# flowerfriend_rev4.net
KiCad netlist of a schematic drawn in EAGLE
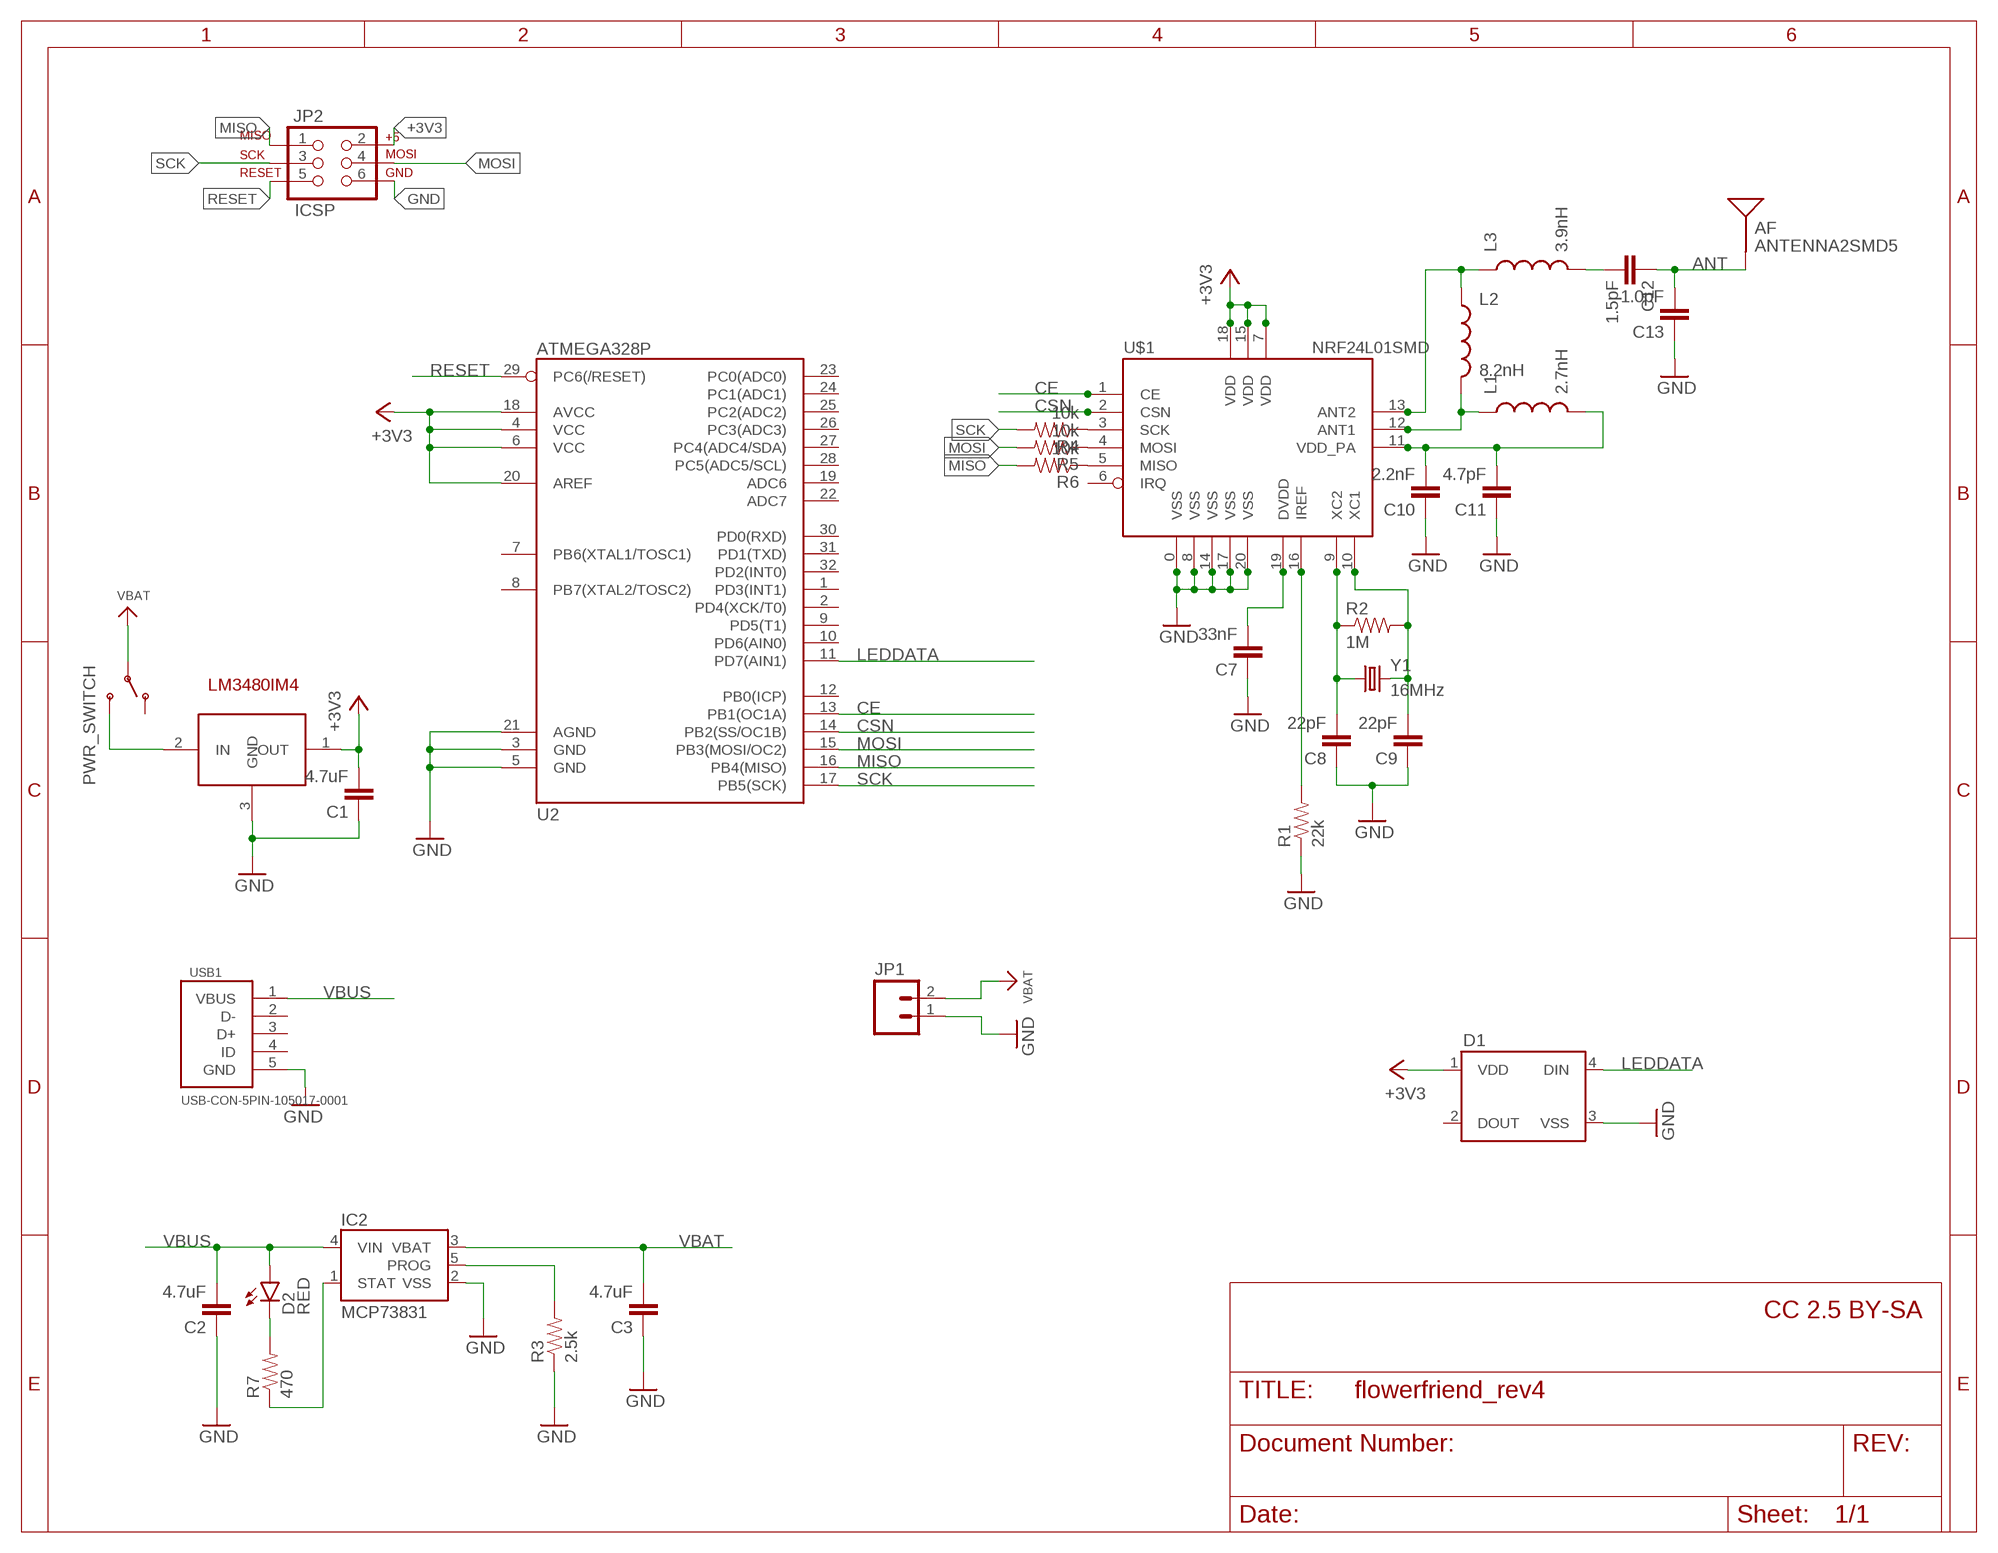
[diagram p0: schematic, sheet 1]

(export (version "E")
  (design (tool "Eeschema 10.0.6"))
  (components
    (comp (ref "AF")
      (value "ANTENNA2SMD5")
      (footprint "eagle-import:ANTENNA-CHIP5")
      (libsource (lib "eagle-import") (part "ANTENNA2SMD5"))
    )
    (comp (ref "C1")
      (value "4.7uF")
      (footprint "eagle-import:0805")
      (libsource (lib "eagle-import") (part "CAP0805"))
    )
    (comp (ref "C2")
      (value "4.7uF")
      (footprint "eagle-import:0805")
      (libsource (lib "eagle-import") (part "CAP0805"))
    )
    (comp (ref "C3")
      (value "4.7uF")
      (footprint "eagle-import:0805")
      (libsource (lib "eagle-import") (part "CAP0805"))
    )
    (comp (ref "C7")
      (value "33nF")
      (footprint "eagle-import:0805")
      (libsource (lib "eagle-import") (part "CAP0805"))
    )
    (comp (ref "C8")
      (value "22pF")
      (footprint "eagle-import:0805")
      (libsource (lib "eagle-import") (part "CAP0805"))
    )
    (comp (ref "C9")
      (value "22pF")
      (footprint "eagle-import:0805")
      (libsource (lib "eagle-import") (part "CAP0805"))
    )
    (comp (ref "C10")
      (value "2.2nF")
      (footprint "eagle-import:0805")
      (libsource (lib "eagle-import") (part "CAP0805"))
    )
    (comp (ref "C11")
      (value "4.7pF")
      (footprint "eagle-import:0805")
      (libsource (lib "eagle-import") (part "CAP0805"))
    )
    (comp (ref "C12")
      (value "1.5pF")
      (footprint "eagle-import:0805")
      (libsource (lib "eagle-import") (part "CAP0805"))
    )
    (comp (ref "C13")
      (value "1.0pF")
      (footprint "eagle-import:0805")
      (libsource (lib "eagle-import") (part "CAP0805"))
    )
    (comp (ref "D1")
      (value "WS2812B")
      (footprint "eagle-import:WS2812B")
      (libsource (lib "eagle-import") (part "WS2812B"))
    )
    (comp (ref "D2")
      (value "RED")
      (footprint "eagle-import:LED-0603")
      (libsource (lib "eagle-import") (part "LED-RED0603"))
    )
    (comp (ref "IC1")
      (value "LM3480IM4")
      (footprint "eagle-import:SOT23-3")
      (libsource (lib "eagle-import") (part "LM3480IM4"))
    )
    (comp (ref "IC2")
      (value "MCP73831")
      (footprint "eagle-import:SOT23-5")
      (libsource (lib "eagle-import") (part "MCP73831"))
    )
    (comp (ref "JP1")
      (value "M02PTH")
      (footprint "eagle-import:1X02")
      (libsource (lib "eagle-import") (part "M02PTH"))
    )
    (comp (ref "JP2")
      (value "ICSP")
      (footprint "eagle-import:2X3")
      (libsource (lib "eagle-import") (part "AVR_SPI_PRG_6PTH"))
    )
    (comp (ref "L1")
      (value "2.7nH")
      (footprint "eagle-import:0805")
      (libsource (lib "eagle-import") (part "INDUCTOR0805"))
    )
    (comp (ref "L2")
      (value "8.2nH")
      (footprint "eagle-import:0805")
      (libsource (lib "eagle-import") (part "INDUCTOR0805"))
    )
    (comp (ref "L3")
      (value "3.9nH")
      (footprint "eagle-import:0805")
      (libsource (lib "eagle-import") (part "INDUCTOR0805"))
    )
    (comp (ref "PWR_SWITCH")
      (value "SWITCH_SPDT")
      (footprint "eagle-import:KPS-1290")
      (libsource (lib "eagle-import") (part "SWITCH_SPDT"))
    )
    (comp (ref "R1")
      (value "22k")
      (footprint "eagle-import:0805")
      (libsource (lib "eagle-import") (part "RESISTOR0805-RES"))
    )
    (comp (ref "R2")
      (value "1M")
      (footprint "eagle-import:0805")
      (libsource (lib "eagle-import") (part "RESISTOR0805-RES"))
    )
    (comp (ref "R3")
      (value "2.5k")
      (footprint "eagle-import:0805")
      (libsource (lib "eagle-import") (part "RESISTOR0805-RES"))
    )
    (comp (ref "R4")
      (value "10k")
      (footprint "eagle-import:0805")
      (libsource (lib "eagle-import") (part "RESISTOR0805-RES"))
    )
    (comp (ref "R5")
      (value "10k")
      (footprint "eagle-import:0805")
      (libsource (lib "eagle-import") (part "RESISTOR0805-RES"))
    )
    (comp (ref "R6")
      (value "10k")
      (footprint "eagle-import:0805")
      (libsource (lib "eagle-import") (part "RESISTOR0805-RES"))
    )
    (comp (ref "R7")
      (value "470")
      (footprint "eagle-import:0805")
      (libsource (lib "eagle-import") (part "RESISTOR0805-RES"))
    )
    (comp (ref "U$1")
      (value "NRF24L01SMD")
      (footprint "eagle-import:QFN20")
      (libsource (lib "eagle-import") (part "NRF24L01SMD"))
    )
    (comp (ref "U2")
      (value "ATMEGA328P")
      (footprint "eagle-import:TQFP32-08")
      (libsource (lib "eagle-import") (part "ATMEGA328_SMT"))
    )
    (comp (ref "USB1")
      (value "USB-CON-5PIN-105017-0001")
      (footprint "eagle-import:USB-MICRO-MOLEX-105017-0001")
      (libsource (lib "eagle-import") (part "USB-CON-5PIN-105017-0001"))
    )
    (comp (ref "Y1")
      (value "16MHz")
      (footprint "eagle-import:CRYSTAL-SMD-5X3")
      (libsource (lib "eagle-import") (part "CRYSTAL5X3"))
    )
  )
  (nets
    (net (code "1") (name "+3V3") (class "Default")
      (node (ref "C1") (pin "2") (pinfunction "2_2") (pintype "passive"))
      (node (ref "D1") (pin "1") (pinfunction "VDD_1") (pintype "power_in"))
      (node (ref "IC1") (pin "1") (pinfunction "OUT_1") (pintype "bidirectional"))
      (node (ref "JP2") (pin "2") (pinfunction "2_2") (pintype "passive"))
      (node (ref "U$1") (pin "15") (pinfunction "VDD_15") (pintype "power_in"))
      (node (ref "U$1") (pin "18") (pinfunction "VDD_18") (pintype "power_in"))
      (node (ref "U$1") (pin "7") (pinfunction "VDD_7") (pintype "power_in"))
      (node (ref "U2") (pin "18") (pinfunction "AVCC_18") (pintype "bidirectional"))
      (node (ref "U2") (pin "20") (pinfunction "AREF_20") (pintype "bidirectional"))
      (node (ref "U2") (pin "4") (pinfunction "VCC_4") (pintype "bidirectional"))
      (node (ref "U2") (pin "6") (pinfunction "VCC_6") (pintype "bidirectional"))
    )
    (net (code "2") (name "/ANT") (class "Default")
      (node (ref "AF") (pin "FEED") (pinfunction "SIGNAL_FEED") (pintype "bidirectional"))
      (node (ref "C12") (pin "1") (pinfunction "1_1") (pintype "passive"))
      (node (ref "C13") (pin "2") (pinfunction "2_2") (pintype "passive"))
    )
    (net (code "3") (name "/CE") (class "Default")
      (node (ref "U$1") (pin "1") (pinfunction "CE_1") (pintype "input"))
      (node (ref "U2") (pin "13") (pinfunction "PB1(OC1A)_13") (pintype "bidirectional"))
    )
    (net (code "4") (name "/CSN") (class "Default")
      (node (ref "U$1") (pin "2") (pinfunction "CSN_2") (pintype "input"))
      (node (ref "U2") (pin "14") (pinfunction "PB2(SS/OC1B)_14") (pintype "bidirectional"))
    )
    (net (code "5") (name "/LEDDATA") (class "Default")
      (node (ref "D1") (pin "4") (pinfunction "DIN_4") (pintype "input"))
      (node (ref "U2") (pin "11") (pinfunction "PD7(AIN1)_11") (pintype "bidirectional"))
    )
    (net (code "6") (name "/VBUS") (class "Default")
      (node (ref "C2") (pin "2") (pinfunction "2_2") (pintype "passive"))
      (node (ref "D2") (pin "A") (pinfunction "A_A") (pintype "passive"))
      (node (ref "IC2") (pin "4") (pinfunction "VIN_4") (pintype "power_in"))
      (node (ref "USB1") (pin "1") (pinfunction "VBUS_1") (pintype "power_in"))
    )
    (net (code "7") (name "GND") (class "Default")
      (node (ref "C1") (pin "1") (pinfunction "1_1") (pintype "passive"))
      (node (ref "C10") (pin "1") (pinfunction "1_1") (pintype "passive"))
      (node (ref "C11") (pin "1") (pinfunction "1_1") (pintype "passive"))
      (node (ref "C13") (pin "1") (pinfunction "1_1") (pintype "passive"))
      (node (ref "C2") (pin "1") (pinfunction "1_1") (pintype "passive"))
      (node (ref "C3") (pin "1") (pinfunction "1_1") (pintype "passive"))
      (node (ref "C7") (pin "1") (pinfunction "1_1") (pintype "passive"))
      (node (ref "C8") (pin "1") (pinfunction "1_1") (pintype "passive"))
      (node (ref "C9") (pin "1") (pinfunction "1_1") (pintype "passive"))
      (node (ref "D1") (pin "3") (pinfunction "VSS_3") (pintype "power_in"))
      (node (ref "IC1") (pin "3") (pinfunction "GND_3") (pintype "bidirectional"))
      (node (ref "IC2") (pin "2") (pinfunction "VSS_2") (pintype "power_in"))
      (node (ref "JP1") (pin "1") (pinfunction "1_1") (pintype "passive"))
      (node (ref "JP2") (pin "6") (pinfunction "6_6") (pintype "passive"))
      (node (ref "R1") (pin "1") (pinfunction "1_1") (pintype "passive"))
      (node (ref "R3") (pin "1") (pinfunction "1_1") (pintype "passive"))
      (node (ref "U$1") (pin "0") (pinfunction "VSS_0") (pintype "power_in"))
      (node (ref "U$1") (pin "14") (pinfunction "VSS_14") (pintype "power_in"))
      (node (ref "U$1") (pin "17") (pinfunction "VSS_17") (pintype "power_in"))
      (node (ref "U$1") (pin "20") (pinfunction "VSS_20") (pintype "power_in"))
      (node (ref "U$1") (pin "8") (pinfunction "VSS_8") (pintype "power_in"))
      (node (ref "U2") (pin "21") (pinfunction "AGND_21") (pintype "bidirectional"))
      (node (ref "U2") (pin "3") (pinfunction "GND_3") (pintype "bidirectional"))
      (node (ref "U2") (pin "5") (pinfunction "GND_5") (pintype "bidirectional"))
      (node (ref "USB1") (pin "5") (pinfunction "GND_5") (pintype "power_in"))
    )
    (net (code "8") (name "MISO") (class "Default")
      (node (ref "JP2") (pin "1") (pinfunction "1_1") (pintype "passive"))
      (node (ref "R6") (pin "2") (pinfunction "2_2") (pintype "passive"))
      (node (ref "U2") (pin "16") (pinfunction "PB4(MISO)_16") (pintype "bidirectional"))
    )
    (net (code "9") (name "MOSI") (class "Default")
      (node (ref "JP2") (pin "4") (pinfunction "4_4") (pintype "passive"))
      (node (ref "R5") (pin "2") (pinfunction "2_2") (pintype "passive"))
      (node (ref "U2") (pin "15") (pinfunction "PB3(MOSI/OC2)_15") (pintype "bidirectional"))
    )
    (net (code "10") (name "Net-(C12-Pad2)") (class "Default")
      (node (ref "C12") (pin "2") (pinfunction "2_2") (pintype "passive"))
      (node (ref "L3") (pin "2") (pinfunction "2_2") (pintype "passive"))
    )
    (net (code "11") (name "Net-(D2-PadC)") (class "Default")
      (node (ref "D2") (pin "C") (pinfunction "C_C") (pintype "passive"))
      (node (ref "R7") (pin "2") (pinfunction "2_2") (pintype "passive"))
    )
    (net (code "12") (name "Net-(IC1-IN)") (class "Default")
      (node (ref "IC1") (pin "2") (pinfunction "IN_2") (pintype "bidirectional"))
      (node (ref "PWR_SWITCH") (pin "S") (pinfunction "S_S") (pintype "passive"))
    )
    (net (code "13") (name "Net-(IC2-PROG)") (class "Default")
      (node (ref "IC2") (pin "5") (pinfunction "PROG_5") (pintype "input"))
      (node (ref "R3") (pin "2") (pinfunction "2_2") (pintype "passive"))
    )
    (net (code "14") (name "Net-(IC2-STAT)") (class "Default")
      (node (ref "IC2") (pin "1") (pinfunction "STAT_1") (pintype "output"))
      (node (ref "R7") (pin "1") (pinfunction "1_1") (pintype "passive"))
    )
    (net (code "15") (name "Net-(U$1-ANT1)") (class "Default")
      (node (ref "L1") (pin "1") (pinfunction "1_1") (pintype "passive"))
      (node (ref "L2") (pin "2") (pinfunction "2_2") (pintype "passive"))
      (node (ref "U$1") (pin "12") (pinfunction "ANT1_12") (pintype "output"))
    )
    (net (code "16") (name "Net-(U$1-ANT2)") (class "Default")
      (node (ref "L2") (pin "1") (pinfunction "1_1") (pintype "passive"))
      (node (ref "L3") (pin "1") (pinfunction "1_1") (pintype "passive"))
      (node (ref "U$1") (pin "13") (pinfunction "ANT2_13") (pintype "output"))
    )
    (net (code "17") (name "Net-(U$1-DVDD)") (class "Default")
      (node (ref "C7") (pin "2") (pinfunction "2_2") (pintype "passive"))
      (node (ref "U$1") (pin "19") (pinfunction "DVDD_19") (pintype "power_in"))
    )
    (net (code "18") (name "Net-(U$1-IREF)") (class "Default")
      (node (ref "R1") (pin "2") (pinfunction "2_2") (pintype "passive"))
      (node (ref "U$1") (pin "16") (pinfunction "IREF_16") (pintype "input"))
    )
    (net (code "19") (name "Net-(U$1-MISO)") (class "Default")
      (node (ref "R6") (pin "1") (pinfunction "1_1") (pintype "passive"))
      (node (ref "U$1") (pin "5") (pinfunction "MISO_5") (pintype "output"))
    )
    (net (code "20") (name "Net-(U$1-MOSI)") (class "Default")
      (node (ref "R5") (pin "1") (pinfunction "1_1") (pintype "passive"))
      (node (ref "U$1") (pin "4") (pinfunction "MOSI_4") (pintype "input"))
    )
    (net (code "21") (name "Net-(U$1-SCK)") (class "Default")
      (node (ref "R4") (pin "1") (pinfunction "1_1") (pintype "passive"))
      (node (ref "U$1") (pin "3") (pinfunction "SCK_3") (pintype "input"))
    )
    (net (code "22") (name "Net-(U$1-VDD_PA)") (class "Default")
      (node (ref "C10") (pin "2") (pinfunction "2_2") (pintype "passive"))
      (node (ref "C11") (pin "2") (pinfunction "2_2") (pintype "passive"))
      (node (ref "L1") (pin "2") (pinfunction "2_2") (pintype "passive"))
      (node (ref "U$1") (pin "11") (pinfunction "VDD_PA_11") (pintype "power_in"))
    )
    (net (code "23") (name "Net-(U$1-XC1)") (class "Default")
      (node (ref "C9") (pin "2") (pinfunction "2_2") (pintype "passive"))
      (node (ref "R2") (pin "2") (pinfunction "2_2") (pintype "passive"))
      (node (ref "U$1") (pin "10") (pinfunction "XC1_10") (pintype "input"))
      (node (ref "Y1") (pin "3") (pinfunction "2_3") (pintype "passive"))
    )
    (net (code "24") (name "Net-(U$1-XC2)") (class "Default")
      (node (ref "C8") (pin "2") (pinfunction "2_2") (pintype "passive"))
      (node (ref "R2") (pin "1") (pinfunction "1_1") (pintype "passive"))
      (node (ref "U$1") (pin "9") (pinfunction "XC2_9") (pintype "input"))
      (node (ref "Y1") (pin "1") (pinfunction "1_1") (pintype "passive"))
    )
    (net (code "25") (name "RESET") (class "Default")
      (node (ref "JP2") (pin "5") (pinfunction "5_5") (pintype "passive"))
      (node (ref "U2") (pin "29") (pinfunction "PC6(/RESET)_29") (pintype "bidirectional"))
    )
    (net (code "26") (name "SCK") (class "Default")
      (node (ref "JP2") (pin "3") (pinfunction "3_3") (pintype "passive"))
      (node (ref "R4") (pin "2") (pinfunction "2_2") (pintype "passive"))
      (node (ref "U2") (pin "17") (pinfunction "PB5(SCK)_17") (pintype "bidirectional"))
    )
    (net (code "27") (name "VBAT") (class "Default")
      (node (ref "C3") (pin "2") (pinfunction "2_2") (pintype "passive"))
      (node (ref "IC2") (pin "3") (pinfunction "VBAT_3") (pintype "power_in"))
      (node (ref "JP1") (pin "2") (pinfunction "2_2") (pintype "passive"))
      (node (ref "PWR_SWITCH") (pin "P") (pinfunction "P_P") (pintype "passive"))
    )
    (net (code "28") (name "unconnected-(D1-DOUT-Pad2)") (class "Default")
      (node (ref "D1") (pin "2") (pinfunction "DOUT_2") (pintype "output"))
    )
    (net (code "29") (name "unconnected-(PWR_SWITCH-PadO)") (class "Default")
      (node (ref "PWR_SWITCH") (pin "O") (pinfunction "O_O") (pintype "passive"))
    )
    (net (code "30") (name "unconnected-(U$1-IRQ-Pad6)") (class "Default")
      (node (ref "U$1") (pin "6") (pinfunction "IRQ_6") (pintype "output"))
    )
    (net (code "31") (name "unconnected-(U2-ADC6-Pad19)") (class "Default")
      (node (ref "U2") (pin "19") (pinfunction "ADC6_19") (pintype "bidirectional"))
    )
    (net (code "32") (name "unconnected-(U2-ADC7-Pad22)") (class "Default")
      (node (ref "U2") (pin "22") (pinfunction "ADC7_22") (pintype "bidirectional"))
    )
    (net (code "33") (name "unconnected-(U2-PB0(ICP)-Pad12)") (class "Default")
      (node (ref "U2") (pin "12") (pinfunction "PB0(ICP)_12") (pintype "bidirectional"))
    )
    (net (code "34") (name "unconnected-(U2-PB6(XTAL1{slash}TOSC1)-Pad7)") (class "Default")
      (node (ref "U2") (pin "7") (pinfunction "PB6(XTAL1/TOSC1)_7") (pintype "bidirectional"))
    )
    (net (code "35") (name "unconnected-(U2-PB7(XTAL2{slash}TOSC2)-Pad8)") (class "Default")
      (node (ref "U2") (pin "8") (pinfunction "PB7(XTAL2/TOSC2)_8") (pintype "bidirectional"))
    )
    (net (code "36") (name "unconnected-(U2-PC0(ADC0)-Pad23)") (class "Default")
      (node (ref "U2") (pin "23") (pinfunction "PC0(ADC0)_23") (pintype "bidirectional"))
    )
    (net (code "37") (name "unconnected-(U2-PC1(ADC1)-Pad24)") (class "Default")
      (node (ref "U2") (pin "24") (pinfunction "PC1(ADC1)_24") (pintype "bidirectional"))
    )
    (net (code "38") (name "unconnected-(U2-PC2(ADC2)-Pad25)") (class "Default")
      (node (ref "U2") (pin "25") (pinfunction "PC2(ADC2)_25") (pintype "bidirectional"))
    )
    (net (code "39") (name "unconnected-(U2-PC3(ADC3)-Pad26)") (class "Default")
      (node (ref "U2") (pin "26") (pinfunction "PC3(ADC3)_26") (pintype "bidirectional"))
    )
    (net (code "40") (name "unconnected-(U2-PC4(ADC4{slash}SDA)-Pad27)") (class "Default")
      (node (ref "U2") (pin "27") (pinfunction "PC4(ADC4/SDA)_27") (pintype "bidirectional"))
    )
    (net (code "41") (name "unconnected-(U2-PC5(ADC5{slash}SCL)-Pad28)") (class "Default")
      (node (ref "U2") (pin "28") (pinfunction "PC5(ADC5/SCL)_28") (pintype "bidirectional"))
    )
    (net (code "42") (name "unconnected-(U2-PD0(RXD)-Pad30)") (class "Default")
      (node (ref "U2") (pin "30") (pinfunction "PD0(RXD)_30") (pintype "bidirectional"))
    )
    (net (code "43") (name "unconnected-(U2-PD1(TXD)-Pad31)") (class "Default")
      (node (ref "U2") (pin "31") (pinfunction "PD1(TXD)_31") (pintype "bidirectional"))
    )
    (net (code "44") (name "unconnected-(U2-PD2(INT0)-Pad32)") (class "Default")
      (node (ref "U2") (pin "32") (pinfunction "PD2(INT0)_32") (pintype "bidirectional"))
    )
    (net (code "45") (name "unconnected-(U2-PD3(INT1)-Pad1)") (class "Default")
      (node (ref "U2") (pin "1") (pinfunction "PD3(INT1)_1") (pintype "bidirectional"))
    )
    (net (code "46") (name "unconnected-(U2-PD4(XCK{slash}T0)-Pad2)") (class "Default")
      (node (ref "U2") (pin "2") (pinfunction "PD4(XCK/T0)_2") (pintype "bidirectional"))
    )
    (net (code "47") (name "unconnected-(U2-PD5(T1)-Pad9)") (class "Default")
      (node (ref "U2") (pin "9") (pinfunction "PD5(T1)_9") (pintype "bidirectional"))
    )
    (net (code "48") (name "unconnected-(U2-PD6(AIN0)-Pad10)") (class "Default")
      (node (ref "U2") (pin "10") (pinfunction "PD6(AIN0)_10") (pintype "bidirectional"))
    )
    (net (code "49") (name "unconnected-(USB1-D+-Pad3)") (class "Default")
      (node (ref "USB1") (pin "3") (pinfunction "D+_3") (pintype "bidirectional"))
    )
    (net (code "50") (name "unconnected-(USB1-D--Pad2)") (class "Default")
      (node (ref "USB1") (pin "2") (pinfunction "D-_2") (pintype "bidirectional"))
    )
    (net (code "51") (name "unconnected-(USB1-ID-Pad4)") (class "Default")
      (node (ref "USB1") (pin "4") (pinfunction "ID_4") (pintype "bidirectional"))
    )
  )
)
